# E-Slushy.net
KiCad netlist of a schematic drawn in EAGLE
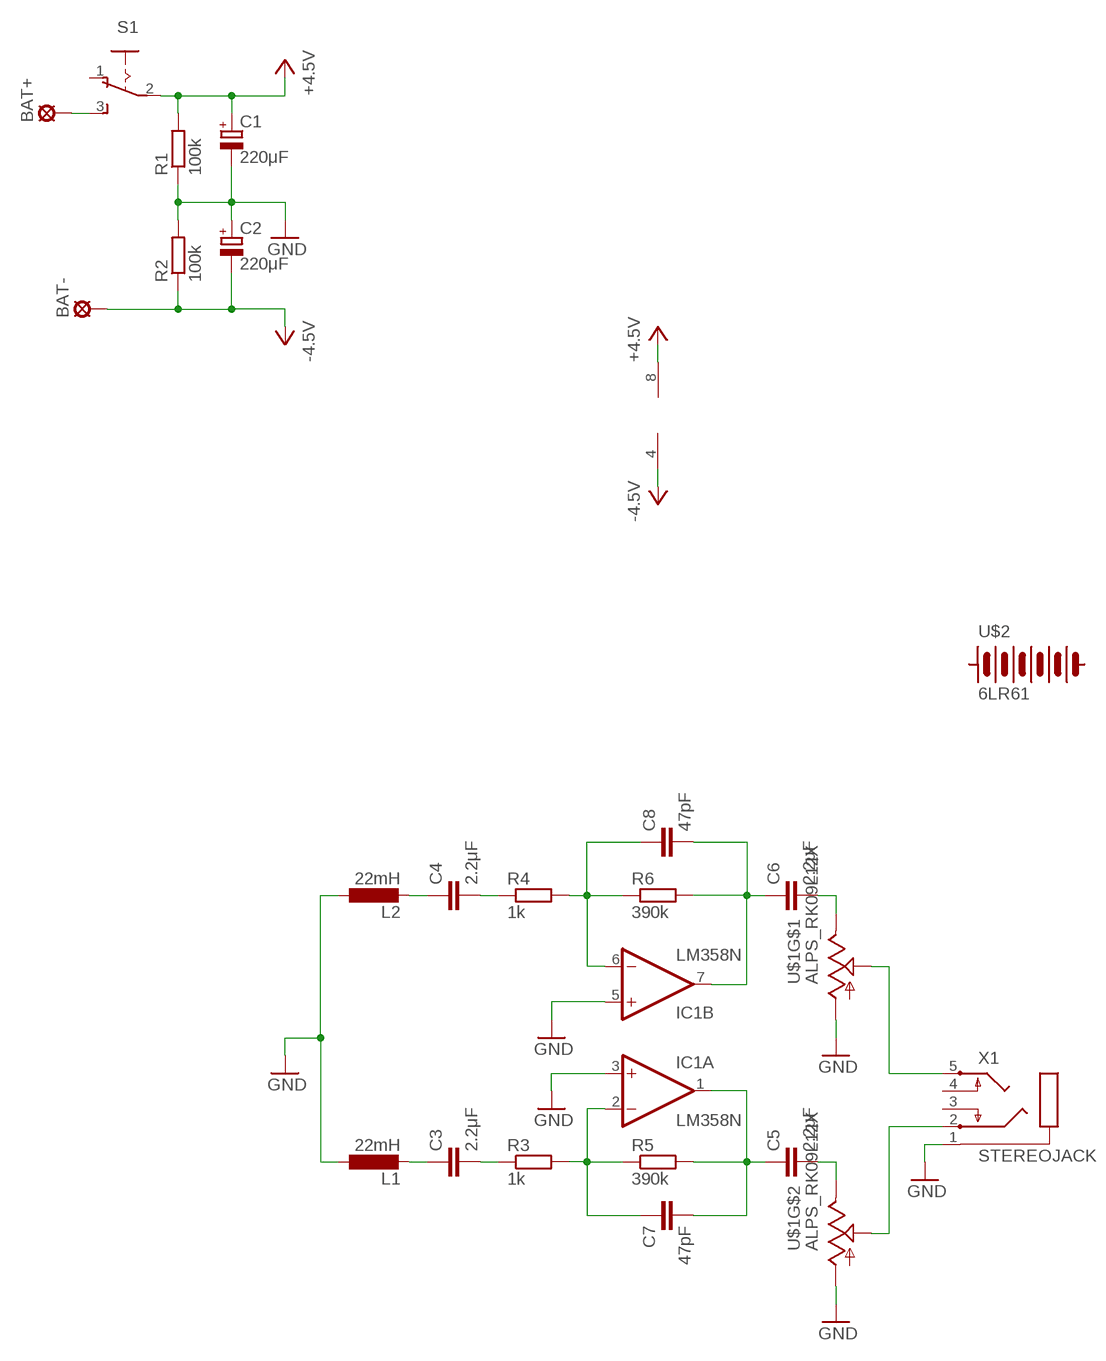
[diagram p0: schematic, sheet 1]

(export (version "E")
  (design (tool "Eeschema 10.0.6"))
  (components
    (comp (ref "BAT+")
      (value "SE14")
      (footprint "eagle-import:SE14")
      (libsource (lib "eagle-import") (part "SE14"))
    )
    (comp (ref "BAT-")
      (value "SE14")
      (footprint "eagle-import:SE14")
      (libsource (lib "eagle-import") (part "SE14"))
    )
    (comp (ref "C1")
      (value "220μF")
      (footprint "eagle-import:PANASONIC_D")
      (libsource (lib "eagle-import") (part "CPOL-EUD"))
    )
    (comp (ref "C2")
      (value "220μF")
      (footprint "eagle-import:PANASONIC_D")
      (libsource (lib "eagle-import") (part "CPOL-EUD"))
    )
    (comp (ref "C3")
      (value "2.2μF")
      (footprint "eagle-import:C1206K")
      (libsource (lib "eagle-import") (part "C-EUC1206K"))
    )
    (comp (ref "C4")
      (value "2.2μF")
      (footprint "eagle-import:C1206K")
      (libsource (lib "eagle-import") (part "C-EUC1206K"))
    )
    (comp (ref "C5")
      (value "2.2μF")
      (footprint "eagle-import:C1206K")
      (libsource (lib "eagle-import") (part "C-EUC1206K"))
    )
    (comp (ref "C6")
      (value "2.2μF")
      (footprint "eagle-import:C1206K")
      (libsource (lib "eagle-import") (part "C-EUC1206K"))
    )
    (comp (ref "C7")
      (value "47pF")
      (footprint "eagle-import:C1206K")
      (libsource (lib "eagle-import") (part "C-EUC1206K"))
    )
    (comp (ref "C8")
      (value "47pF")
      (footprint "eagle-import:C1206K")
      (libsource (lib "eagle-import") (part "C-EUC1206K"))
    )
    (comp (ref "IC1")
      (value "LM358N")
      (footprint "eagle-import:DIL08")
      (libsource (lib "eagle-import") (part "LM358N"))
    )
    (comp (ref "L1")
      (value "22mH")
      (footprint "eagle-import:6000-XXXX-RC")
      (libsource (lib "eagle-import") (part "L-EU6000-XXX-RC"))
    )
    (comp (ref "L2")
      (value "22mH")
      (footprint "eagle-import:6000-XXXX-RC")
      (libsource (lib "eagle-import") (part "L-EU6000-XXX-RC"))
    )
    (comp (ref "R1")
      (value "100k")
      (footprint "eagle-import:R1206")
      (libsource (lib "eagle-import") (part "R-EU_R1206"))
    )
    (comp (ref "R2")
      (value "100k")
      (footprint "eagle-import:R1206")
      (libsource (lib "eagle-import") (part "R-EU_R1206"))
    )
    (comp (ref "R3")
      (value "1k")
      (footprint "eagle-import:R1206")
      (libsource (lib "eagle-import") (part "R-EU_R1206"))
    )
    (comp (ref "R4")
      (value "1k")
      (footprint "eagle-import:R1206")
      (libsource (lib "eagle-import") (part "R-EU_R1206"))
    )
    (comp (ref "R5")
      (value "390k")
      (footprint "eagle-import:R1206")
      (libsource (lib "eagle-import") (part "R-EU_R1206"))
    )
    (comp (ref "R6")
      (value "390k")
      (footprint "eagle-import:R1206")
      (libsource (lib "eagle-import") (part "R-EU_R1206"))
    )
    (comp (ref "S1")
      (value "255SB")
      (footprint "eagle-import:255SB")
      (libsource (lib "eagle-import") (part "255SB"))
    )
    (comp (ref "U$1")
      (value "ALPS_RK09L12X")
      (footprint "eagle-import:RK09L12")
      (libsource (lib "eagle-import") (part "ALPS_RK09L12X"))
    )
    (comp (ref "U$2")
      (value "6LR61")
      (footprint "eagle-import:6LR61")
      (libsource (lib "eagle-import") (part "6LR61"))
    )
    (comp (ref "X1")
      (value "STEREOJACK")
      (footprint "eagle-import:STX3100")
      (libsource (lib "eagle-import") (part "STEREOJACK"))
    )
  )
  (nets
    (net (code "1") (name "+4.5V") (class "Default")
      (node (ref "C1") (pin "+") (pinfunction "+_+") (pintype "passive"))
      (node (ref "IC1") (pin "8") (pinfunction "V+_8") (pintype "power_in"))
      (node (ref "R1") (pin "2") (pinfunction "2_2") (pintype "passive"))
      (node (ref "S1") (pin "2") (pinfunction "P_2") (pintype "passive"))
    )
    (net (code "2") (name "-4.5V") (class "Default")
      (node (ref "BAT-") (pin "MP") (pinfunction "MP_MP") (pintype "passive"))
      (node (ref "C2") (pin "-") (pinfunction "-_-") (pintype "passive"))
      (node (ref "IC1") (pin "4") (pinfunction "V-_4") (pintype "power_in"))
      (node (ref "R2") (pin "1") (pinfunction "1_1") (pintype "passive"))
    )
    (net (code "3") (name "GND") (class "Default")
      (node (ref "C1") (pin "-") (pinfunction "-_-") (pintype "passive"))
      (node (ref "C2") (pin "+") (pinfunction "+_+") (pintype "passive"))
      (node (ref "IC1") (pin "3") (pinfunction "+IN_3") (pintype "input"))
      (node (ref "IC1") (pin "5") (pinfunction "+IN_5") (pintype "input"))
      (node (ref "L1") (pin "1") (pinfunction "1_1") (pintype "passive"))
      (node (ref "L2") (pin "1") (pinfunction "1_1") (pintype "passive"))
      (node (ref "R1") (pin "1") (pinfunction "1_1") (pintype "passive"))
      (node (ref "R2") (pin "2") (pinfunction "2_2") (pintype "passive"))
      (node (ref "U$1") (pin "A1") (pinfunction "1_A1") (pintype "passive"))
      (node (ref "U$1") (pin "B1") (pinfunction "1_B1") (pintype "passive"))
      (node (ref "X1") (pin "1") (pinfunction "1_1") (pintype "passive"))
    )
    (net (code "4") (name "Net-(C3-Pad1)") (class "Default")
      (node (ref "C3") (pin "1") (pinfunction "1_1") (pintype "passive"))
      (node (ref "L1") (pin "2") (pinfunction "2_2") (pintype "passive"))
    )
    (net (code "5") (name "Net-(C3-Pad2)") (class "Default")
      (node (ref "C3") (pin "2") (pinfunction "2_2") (pintype "passive"))
      (node (ref "R3") (pin "1") (pinfunction "1_1") (pintype "passive"))
    )
    (net (code "6") (name "Net-(C4-Pad1)") (class "Default")
      (node (ref "C4") (pin "1") (pinfunction "1_1") (pintype "passive"))
      (node (ref "L2") (pin "2") (pinfunction "2_2") (pintype "passive"))
    )
    (net (code "7") (name "Net-(C4-Pad2)") (class "Default")
      (node (ref "C4") (pin "2") (pinfunction "2_2") (pintype "passive"))
      (node (ref "R4") (pin "1") (pinfunction "1_1") (pintype "passive"))
    )
    (net (code "8") (name "Net-(IC1A--IN)") (class "Default")
      (node (ref "C7") (pin "1") (pinfunction "1_1") (pintype "passive"))
      (node (ref "IC1") (pin "2") (pinfunction "-IN_2") (pintype "input"))
      (node (ref "R3") (pin "2") (pinfunction "2_2") (pintype "passive"))
      (node (ref "R5") (pin "1") (pinfunction "1_1") (pintype "passive"))
    )
    (net (code "9") (name "Net-(IC1A-OUT)") (class "Default")
      (node (ref "C5") (pin "1") (pinfunction "1_1") (pintype "passive"))
      (node (ref "C7") (pin "2") (pinfunction "2_2") (pintype "passive"))
      (node (ref "IC1") (pin "1") (pinfunction "OUT_1") (pintype "output"))
      (node (ref "R5") (pin "2") (pinfunction "2_2") (pintype "passive"))
    )
    (net (code "10") (name "Net-(IC1B--IN)") (class "Default")
      (node (ref "C8") (pin "1") (pinfunction "1_1") (pintype "passive"))
      (node (ref "IC1") (pin "6") (pinfunction "-IN_6") (pintype "input"))
      (node (ref "R4") (pin "2") (pinfunction "2_2") (pintype "passive"))
      (node (ref "R6") (pin "1") (pinfunction "1_1") (pintype "passive"))
    )
    (net (code "11") (name "Net-(IC1B-OUT)") (class "Default")
      (node (ref "C6") (pin "1") (pinfunction "1_1") (pintype "passive"))
      (node (ref "C8") (pin "2") (pinfunction "2_2") (pintype "passive"))
      (node (ref "IC1") (pin "7") (pinfunction "OUT_7") (pintype "output"))
      (node (ref "R6") (pin "2") (pinfunction "2_2") (pintype "passive"))
    )
    (net (code "12") (name "Net-(S1-S)") (class "Default")
      (node (ref "BAT+") (pin "MP") (pinfunction "MP_MP") (pintype "passive"))
      (node (ref "S1") (pin "3") (pinfunction "S_3") (pintype "passive"))
    )
    (net (code "13") (name "Net-(U$1A-2)") (class "Default")
      (node (ref "U$1") (pin "A2") (pinfunction "2_A2") (pintype "passive"))
      (node (ref "X1") (pin "5") (pinfunction "5_5") (pintype "passive"))
    )
    (net (code "14") (name "Net-(U$1A-3)") (class "Default")
      (node (ref "C6") (pin "2") (pinfunction "2_2") (pintype "passive"))
      (node (ref "U$1") (pin "A3") (pinfunction "3_A3") (pintype "passive"))
    )
    (net (code "15") (name "Net-(U$1B-2)") (class "Default")
      (node (ref "U$1") (pin "B2") (pinfunction "2_B2") (pintype "passive"))
      (node (ref "X1") (pin "2") (pinfunction "2_2") (pintype "passive"))
    )
    (net (code "16") (name "Net-(U$1B-3)") (class "Default")
      (node (ref "C5") (pin "2") (pinfunction "2_2") (pintype "passive"))
      (node (ref "U$1") (pin "B3") (pinfunction "3_B3") (pintype "passive"))
    )
    (net (code "17") (name "unconnected-(S1-O-Pad1)") (class "Default")
      (node (ref "S1") (pin "1") (pinfunction "O_1") (pintype "passive"))
    )
    (net (code "18") (name "unconnected-(X1-Pad3)") (class "Default")
      (node (ref "X1") (pin "3") (pinfunction "3_3") (pintype "passive"))
    )
    (net (code "19") (name "unconnected-(X1-Pad4)") (class "Default")
      (node (ref "X1") (pin "4") (pinfunction "4_4") (pintype "passive"))
    )
  )
)
